# Smart_Home.net
KiCad netlist of a schematic drawn in EAGLE
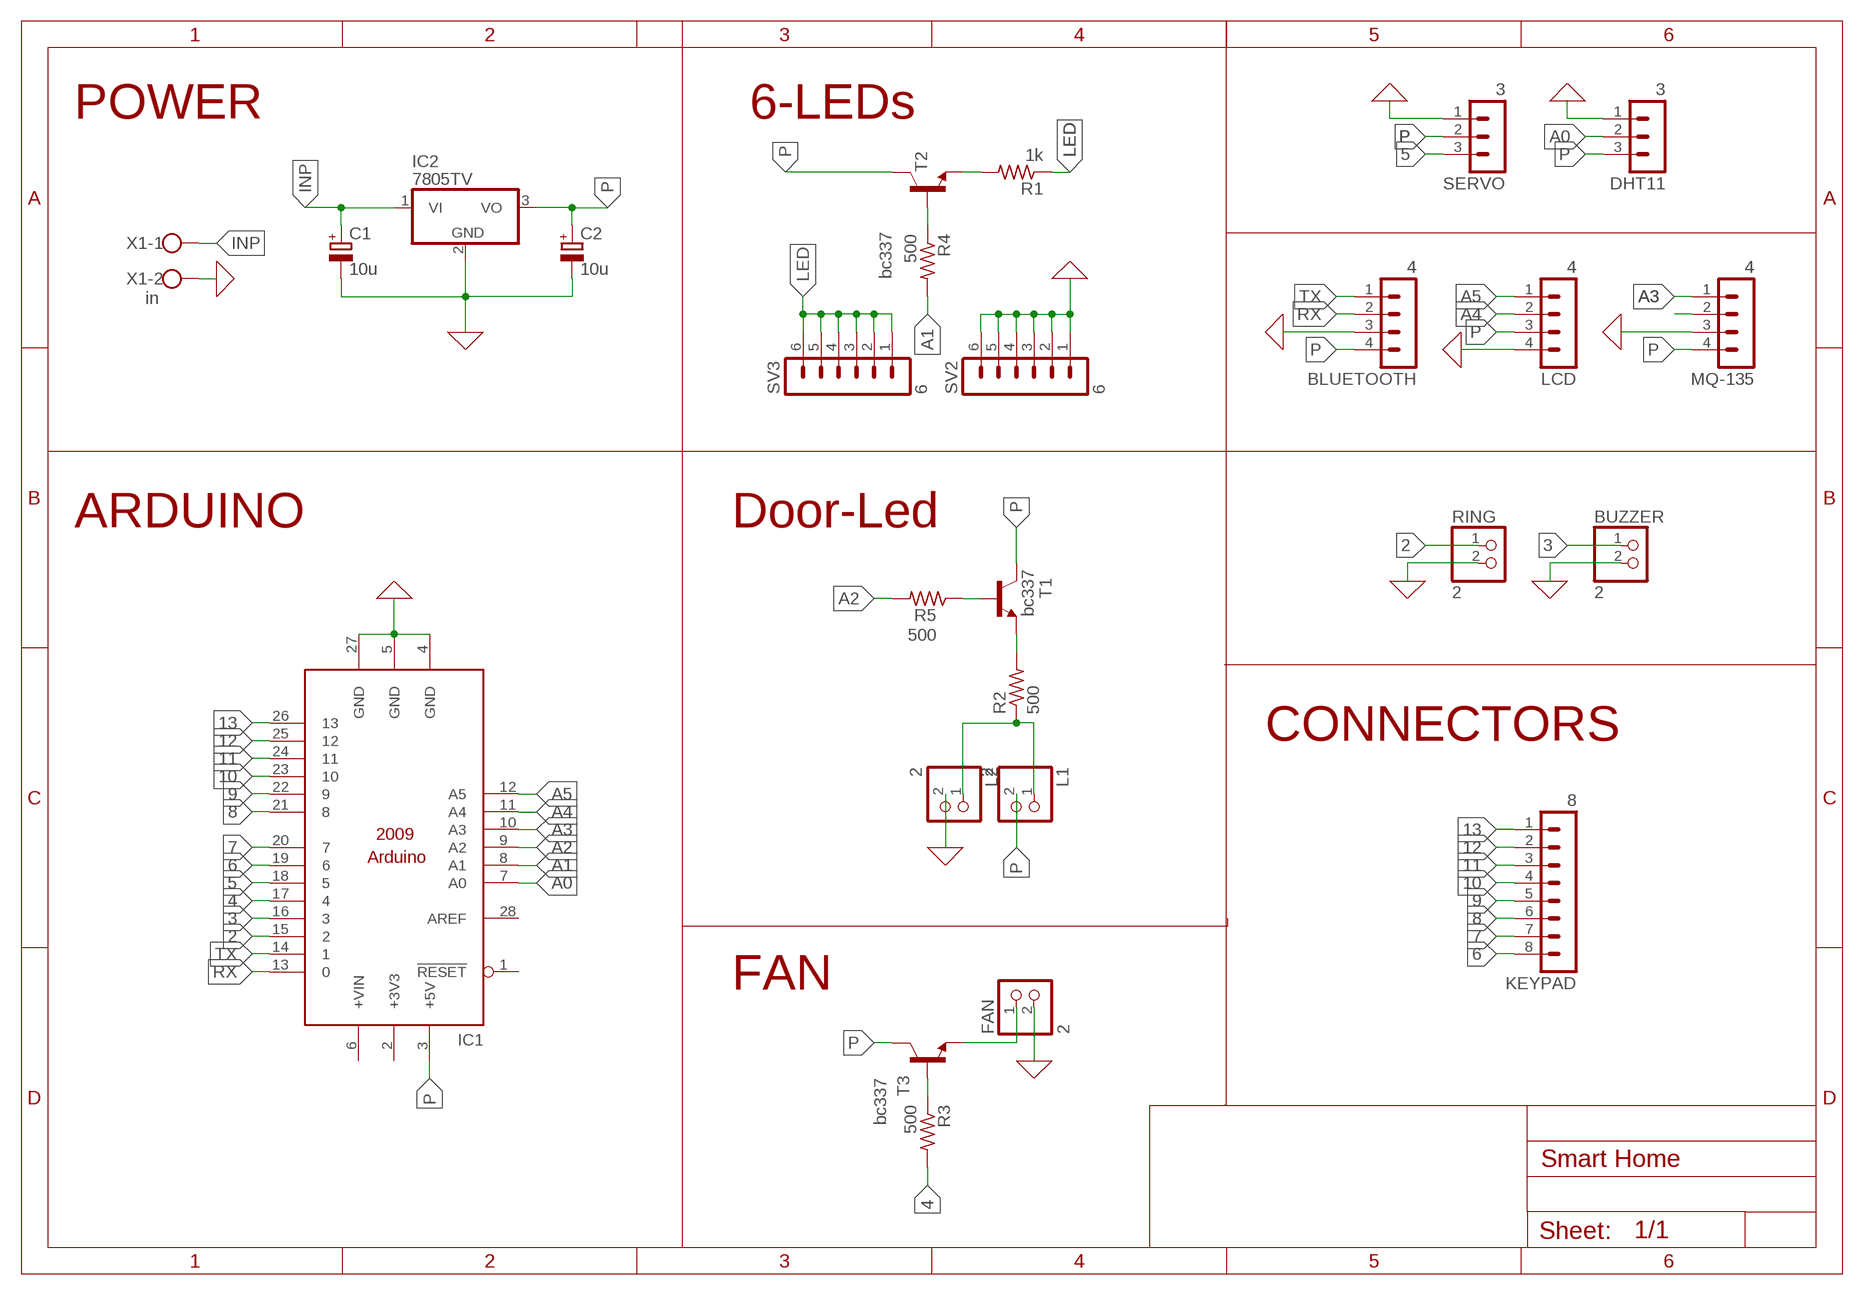
[diagram p0: schematic, sheet 1]

(export (version "E")
  (design (tool "Eeschema 10.0.6"))
  (components
    (comp (ref "BLUETOOTH")
      (value "4")
      (footprint "eagle-import:MA04-1")
      (libsource (lib "eagle-import") (part "MA04-1"))
    )
    (comp (ref "BUZZER")
      (value "2")
      (footprint "eagle-import:1X02")
      (libsource (lib "eagle-import") (part "PINHD-1X2"))
    )
    (comp (ref "C1")
      (value "10u")
      (footprint "eagle-import:E2,5-6")
      (libsource (lib "eagle-import") (part "CPOL-EUE2.5-6"))
    )
    (comp (ref "C2")
      (value "10u")
      (footprint "eagle-import:E2,5-6")
      (libsource (lib "eagle-import") (part "CPOL-EUE2.5-6"))
    )
    (comp (ref "DHT11")
      (value "3")
      (footprint "eagle-import:MA03-1")
      (libsource (lib "eagle-import") (part "MA03-1"))
    )
    (comp (ref "FAN")
      (value "2")
      (footprint "eagle-import:1X02")
      (libsource (lib "eagle-import") (part "PINHD-1X2"))
    )
    (comp (ref "IC1")
      (value "uno")
      (footprint "eagle-import:ARDUINO2009_2")
      (libsource (lib "eagle-import") (part "ARDUINO2009_12"))
    )
    (comp (ref "IC2")
      (value "7805TV")
      (footprint "eagle-import:TO220V")
      (libsource (lib "eagle-import") (part "78TV05"))
    )
    (comp (ref "KEYPAD")
      (value "8")
      (footprint "eagle-import:MA08-1")
      (libsource (lib "eagle-import") (part "MA08-1"))
    )
    (comp (ref "L1")
      (value "2")
      (footprint "eagle-import:1X02")
      (libsource (lib "eagle-import") (part "PINHD-1X2"))
    )
    (comp (ref "L2")
      (value "2")
      (footprint "eagle-import:1X02")
      (libsource (lib "eagle-import") (part "PINHD-1X2"))
    )
    (comp (ref "LCD")
      (value "4")
      (footprint "eagle-import:MA04-1")
      (libsource (lib "eagle-import") (part "MA04-1"))
    )
    (comp (ref "MQ-135")
      (value "4")
      (footprint "eagle-import:MA04-1")
      (libsource (lib "eagle-import") (part "MA04-1"))
    )
    (comp (ref "R1")
      (value "1k")
      (footprint "eagle-import:0207_10")
      (libsource (lib "eagle-import") (part "R-US_0207/10"))
    )
    (comp (ref "R2")
      (value "500")
      (footprint "eagle-import:0207_10")
      (libsource (lib "eagle-import") (part "R-US_0207/10"))
    )
    (comp (ref "R3")
      (value "500")
      (footprint "eagle-import:0207_10")
      (libsource (lib "eagle-import") (part "R-US_0207/10"))
    )
    (comp (ref "R4")
      (value "500")
      (footprint "eagle-import:0207_10")
      (libsource (lib "eagle-import") (part "R-US_0207/10"))
    )
    (comp (ref "R5")
      (value "500")
      (footprint "eagle-import:0207_10")
      (libsource (lib "eagle-import") (part "R-US_0207/10"))
    )
    (comp (ref "RING")
      (value "2")
      (footprint "eagle-import:1X02")
      (libsource (lib "eagle-import") (part "PINHD-1X2"))
    )
    (comp (ref "SERVO")
      (value "3")
      (footprint "eagle-import:MA03-1")
      (libsource (lib "eagle-import") (part "MA03-1"))
    )
    (comp (ref "SV2")
      (value "6")
      (footprint "eagle-import:MA06-1")
      (libsource (lib "eagle-import") (part "MA06-1"))
    )
    (comp (ref "SV3")
      (value "6")
      (footprint "eagle-import:MA06-1")
      (libsource (lib "eagle-import") (part "MA06-1"))
    )
    (comp (ref "T1")
      (value "bc337")
      (footprint "eagle-import:TO92-CBE")
      (libsource (lib "eagle-import") (part "-NPN-TO92-CBEBC337-16"))
    )
    (comp (ref "T2")
      (value "bc337")
      (footprint "eagle-import:TO92-CBE")
      (libsource (lib "eagle-import") (part "-NPN-TO92-CBEBC337-16"))
    )
    (comp (ref "T3")
      (value "bc337")
      (footprint "eagle-import:TO92-CBE")
      (libsource (lib "eagle-import") (part "-NPN-TO92-CBEBC337-16"))
    )
    (comp (ref "X1")
      (value "in")
      (footprint "eagle-import:W237-102")
      (fields (field (name "MPN") "237-102"))
      (libsource (lib "eagle-import") (part "W237-102"))
    )
  )
  (nets
    (net (code "1") (name "/+3V3") (class "Default")
      (node (ref "IC1") (pin "2") (pinfunction "+3V3_2") (pintype "power_in"))
    )
    (net (code "2") (name "2") (class "Default")
      (node (ref "IC1") (pin "15") (pinfunction "2_15") (pintype "bidirectional"))
      (node (ref "RING") (pin "1") (pinfunction "1_1") (pintype "passive"))
    )
    (net (code "3") (name "3") (class "Default")
      (node (ref "BUZZER") (pin "1") (pinfunction "1_1") (pintype "passive"))
      (node (ref "IC1") (pin "16") (pinfunction "3_16") (pintype "bidirectional"))
    )
    (net (code "4") (name "4") (class "Default")
      (node (ref "IC1") (pin "17") (pinfunction "4_17") (pintype "bidirectional"))
      (node (ref "R3") (pin "2") (pinfunction "2_2") (pintype "passive"))
    )
    (net (code "5") (name "5") (class "Default")
      (node (ref "IC1") (pin "18") (pinfunction "5_18") (pintype "bidirectional"))
      (node (ref "SERVO") (pin "3") (pinfunction "3_3") (pintype "passive"))
    )
    (net (code "6") (name "6") (class "Default")
      (node (ref "IC1") (pin "19") (pinfunction "6_19") (pintype "bidirectional"))
      (node (ref "KEYPAD") (pin "8") (pinfunction "8_8") (pintype "passive"))
    )
    (net (code "7") (name "7") (class "Default")
      (node (ref "IC1") (pin "20") (pinfunction "7_20") (pintype "bidirectional"))
      (node (ref "KEYPAD") (pin "7") (pinfunction "7_7") (pintype "passive"))
    )
    (net (code "8") (name "8") (class "Default")
      (node (ref "IC1") (pin "21") (pinfunction "8_21") (pintype "bidirectional"))
      (node (ref "KEYPAD") (pin "6") (pinfunction "6_6") (pintype "passive"))
    )
    (net (code "9") (name "9") (class "Default")
      (node (ref "IC1") (pin "22") (pinfunction "9_22") (pintype "bidirectional"))
      (node (ref "KEYPAD") (pin "5") (pinfunction "5_5") (pintype "passive"))
    )
    (net (code "10") (name "10") (class "Default")
      (node (ref "IC1") (pin "23") (pinfunction "10_23") (pintype "bidirectional"))
      (node (ref "KEYPAD") (pin "4") (pinfunction "4_4") (pintype "passive"))
    )
    (net (code "11") (name "11") (class "Default")
      (node (ref "IC1") (pin "24") (pinfunction "11_24") (pintype "bidirectional"))
      (node (ref "KEYPAD") (pin "3") (pinfunction "3_3") (pintype "passive"))
    )
    (net (code "12") (name "12") (class "Default")
      (node (ref "IC1") (pin "25") (pinfunction "12_25") (pintype "bidirectional"))
      (node (ref "KEYPAD") (pin "2") (pinfunction "2_2") (pintype "passive"))
    )
    (net (code "13") (name "13") (class "Default")
      (node (ref "IC1") (pin "26") (pinfunction "13_26") (pintype "bidirectional"))
      (node (ref "KEYPAD") (pin "1") (pinfunction "1_1") (pintype "passive"))
    )
    (net (code "14") (name "A0") (class "Default")
      (node (ref "DHT11") (pin "2") (pinfunction "2_2") (pintype "passive"))
      (node (ref "IC1") (pin "7") (pinfunction "A0_7") (pintype "bidirectional"))
    )
    (net (code "15") (name "A1") (class "Default")
      (node (ref "IC1") (pin "8") (pinfunction "A1_8") (pintype "bidirectional"))
      (node (ref "R4") (pin "2") (pinfunction "2_2") (pintype "passive"))
    )
    (net (code "16") (name "A2") (class "Default")
      (node (ref "IC1") (pin "9") (pinfunction "A2_9") (pintype "bidirectional"))
      (node (ref "R5") (pin "2") (pinfunction "2_2") (pintype "passive"))
    )
    (net (code "17") (name "A3") (class "Default")
      (node (ref "IC1") (pin "10") (pinfunction "A3_10") (pintype "bidirectional"))
      (node (ref "MQ-135") (pin "1") (pinfunction "1_1") (pintype "passive"))
    )
    (net (code "18") (name "A4") (class "Default")
      (node (ref "IC1") (pin "11") (pinfunction "A4_11") (pintype "bidirectional"))
      (node (ref "LCD") (pin "2") (pinfunction "2_2") (pintype "passive"))
    )
    (net (code "19") (name "A5") (class "Default")
      (node (ref "IC1") (pin "12") (pinfunction "A5_12") (pintype "bidirectional"))
      (node (ref "LCD") (pin "1") (pinfunction "1_1") (pintype "passive"))
    )
    (net (code "20") (name "GND") (class "Default")
      (node (ref "BLUETOOTH") (pin "3") (pinfunction "3_3") (pintype "passive"))
      (node (ref "BUZZER") (pin "2") (pinfunction "2_2") (pintype "passive"))
      (node (ref "C1") (pin "-") (pinfunction "-_-") (pintype "passive"))
      (node (ref "C2") (pin "-") (pinfunction "-_-") (pintype "passive"))
      (node (ref "DHT11") (pin "1") (pinfunction "1_1") (pintype "passive"))
      (node (ref "FAN") (pin "2") (pinfunction "2_2") (pintype "passive"))
      (node (ref "IC1") (pin "27") (pinfunction "GND_27") (pintype "power_in"))
      (node (ref "IC1") (pin "4") (pinfunction "GND_4") (pintype "power_in"))
      (node (ref "IC1") (pin "5") (pinfunction "GND_5") (pintype "power_in"))
      (node (ref "IC2") (pin "2") (pinfunction "GND_2") (pintype "passive"))
      (node (ref "L2") (pin "2") (pinfunction "2_2") (pintype "passive"))
      (node (ref "LCD") (pin "4") (pinfunction "4_4") (pintype "passive"))
      (node (ref "MQ-135") (pin "3") (pinfunction "3_3") (pintype "passive"))
      (node (ref "RING") (pin "2") (pinfunction "2_2") (pintype "passive"))
      (node (ref "SERVO") (pin "1") (pinfunction "1_1") (pintype "passive"))
      (node (ref "SV2") (pin "1") (pinfunction "1_1") (pintype "passive"))
      (node (ref "SV2") (pin "2") (pinfunction "2_2") (pintype "passive"))
      (node (ref "SV2") (pin "3") (pinfunction "3_3") (pintype "passive"))
      (node (ref "SV2") (pin "4") (pinfunction "4_4") (pintype "passive"))
      (node (ref "SV2") (pin "5") (pinfunction "5_5") (pintype "passive"))
      (node (ref "SV2") (pin "6") (pinfunction "6_6") (pintype "passive"))
      (node (ref "X1") (pin "2") (pinfunction "KL_2") (pintype "passive"))
    )
    (net (code "21") (name "INP") (class "Default")
      (node (ref "C1") (pin "+") (pinfunction "+_+") (pintype "passive"))
      (node (ref "IC2") (pin "1") (pinfunction "VI_1") (pintype "input"))
      (node (ref "X1") (pin "1") (pinfunction "KL_1") (pintype "passive"))
    )
    (net (code "22") (name "LED") (class "Default")
      (node (ref "R1") (pin "1") (pinfunction "1_1") (pintype "passive"))
      (node (ref "SV3") (pin "1") (pinfunction "1_1") (pintype "passive"))
      (node (ref "SV3") (pin "2") (pinfunction "2_2") (pintype "passive"))
      (node (ref "SV3") (pin "3") (pinfunction "3_3") (pintype "passive"))
      (node (ref "SV3") (pin "4") (pinfunction "4_4") (pintype "passive"))
      (node (ref "SV3") (pin "5") (pinfunction "5_5") (pintype "passive"))
      (node (ref "SV3") (pin "6") (pinfunction "6_6") (pintype "passive"))
    )
    (net (code "23") (name "Net-(FAN-Pad1)") (class "Default")
      (node (ref "FAN") (pin "1") (pinfunction "1_1") (pintype "passive"))
      (node (ref "T3") (pin "E") (pinfunction "E_E") (pintype "passive"))
    )
    (net (code "24") (name "Net-(L1-Pad1)") (class "Default")
      (node (ref "L1") (pin "1") (pinfunction "1_1") (pintype "passive"))
      (node (ref "L2") (pin "1") (pinfunction "1_1") (pintype "passive"))
      (node (ref "R2") (pin "1") (pinfunction "1_1") (pintype "passive"))
    )
    (net (code "25") (name "Net-(R1-Pad2)") (class "Default")
      (node (ref "R1") (pin "2") (pinfunction "2_2") (pintype "passive"))
      (node (ref "T2") (pin "E") (pinfunction "E_E") (pintype "passive"))
    )
    (net (code "26") (name "Net-(R2-Pad2)") (class "Default")
      (node (ref "R2") (pin "2") (pinfunction "2_2") (pintype "passive"))
      (node (ref "T1") (pin "E") (pinfunction "E_E") (pintype "passive"))
    )
    (net (code "27") (name "Net-(R3-Pad1)") (class "Default")
      (node (ref "R3") (pin "1") (pinfunction "1_1") (pintype "passive"))
      (node (ref "T3") (pin "B") (pinfunction "B_B") (pintype "passive"))
    )
    (net (code "28") (name "Net-(R4-Pad1)") (class "Default")
      (node (ref "R4") (pin "1") (pinfunction "1_1") (pintype "passive"))
      (node (ref "T2") (pin "B") (pinfunction "B_B") (pintype "passive"))
    )
    (net (code "29") (name "Net-(R5-Pad1)") (class "Default")
      (node (ref "R5") (pin "1") (pinfunction "1_1") (pintype "passive"))
      (node (ref "T1") (pin "B") (pinfunction "B_B") (pintype "passive"))
    )
    (net (code "30") (name "P") (class "Default")
      (node (ref "BLUETOOTH") (pin "4") (pinfunction "4_4") (pintype "passive"))
      (node (ref "C2") (pin "+") (pinfunction "+_+") (pintype "passive"))
      (node (ref "DHT11") (pin "3") (pinfunction "3_3") (pintype "passive"))
      (node (ref "IC1") (pin "3") (pinfunction "+5V_3") (pintype "power_in"))
      (node (ref "IC2") (pin "3") (pinfunction "VO_3") (pintype "passive"))
      (node (ref "L1") (pin "2") (pinfunction "2_2") (pintype "passive"))
      (node (ref "LCD") (pin "3") (pinfunction "3_3") (pintype "passive"))
      (node (ref "MQ-135") (pin "4") (pinfunction "4_4") (pintype "passive"))
      (node (ref "SERVO") (pin "2") (pinfunction "2_2") (pintype "passive"))
      (node (ref "T1") (pin "C") (pinfunction "C_C") (pintype "passive"))
      (node (ref "T2") (pin "C") (pinfunction "C_C") (pintype "passive"))
      (node (ref "T3") (pin "C") (pinfunction "C_C") (pintype "passive"))
    )
    (net (code "31") (name "RX") (class "Default")
      (node (ref "BLUETOOTH") (pin "2") (pinfunction "2_2") (pintype "passive"))
      (node (ref "IC1") (pin "13") (pinfunction "0_13") (pintype "bidirectional"))
    )
    (net (code "32") (name "TX") (class "Default")
      (node (ref "BLUETOOTH") (pin "1") (pinfunction "1_1") (pintype "passive"))
      (node (ref "IC1") (pin "14") (pinfunction "1_14") (pintype "bidirectional"))
    )
    (net (code "33") (name "unconnected-(IC1-+VIN-Pad6)") (class "Default")
      (node (ref "IC1") (pin "6") (pinfunction "+VIN_6") (pintype "bidirectional"))
    )
    (net (code "34") (name "unconnected-(IC1-AREF-Pad28)") (class "Default")
      (node (ref "IC1") (pin "28") (pinfunction "AREF_28") (pintype "bidirectional"))
    )
    (net (code "35") (name "unconnected-(IC1-~{RESET}-Pad1)") (class "Default")
      (node (ref "IC1") (pin "1") (pinfunction "~{RESET}_1") (pintype "bidirectional"))
    )
    (net (code "36") (name "unconnected-(MQ-135-Pad2)") (class "Default")
      (node (ref "MQ-135") (pin "2") (pinfunction "2_2") (pintype "passive"))
    )
  )
)
